# EEPROM.net
KiCad netlist of a schematic drawn in Altium Designer
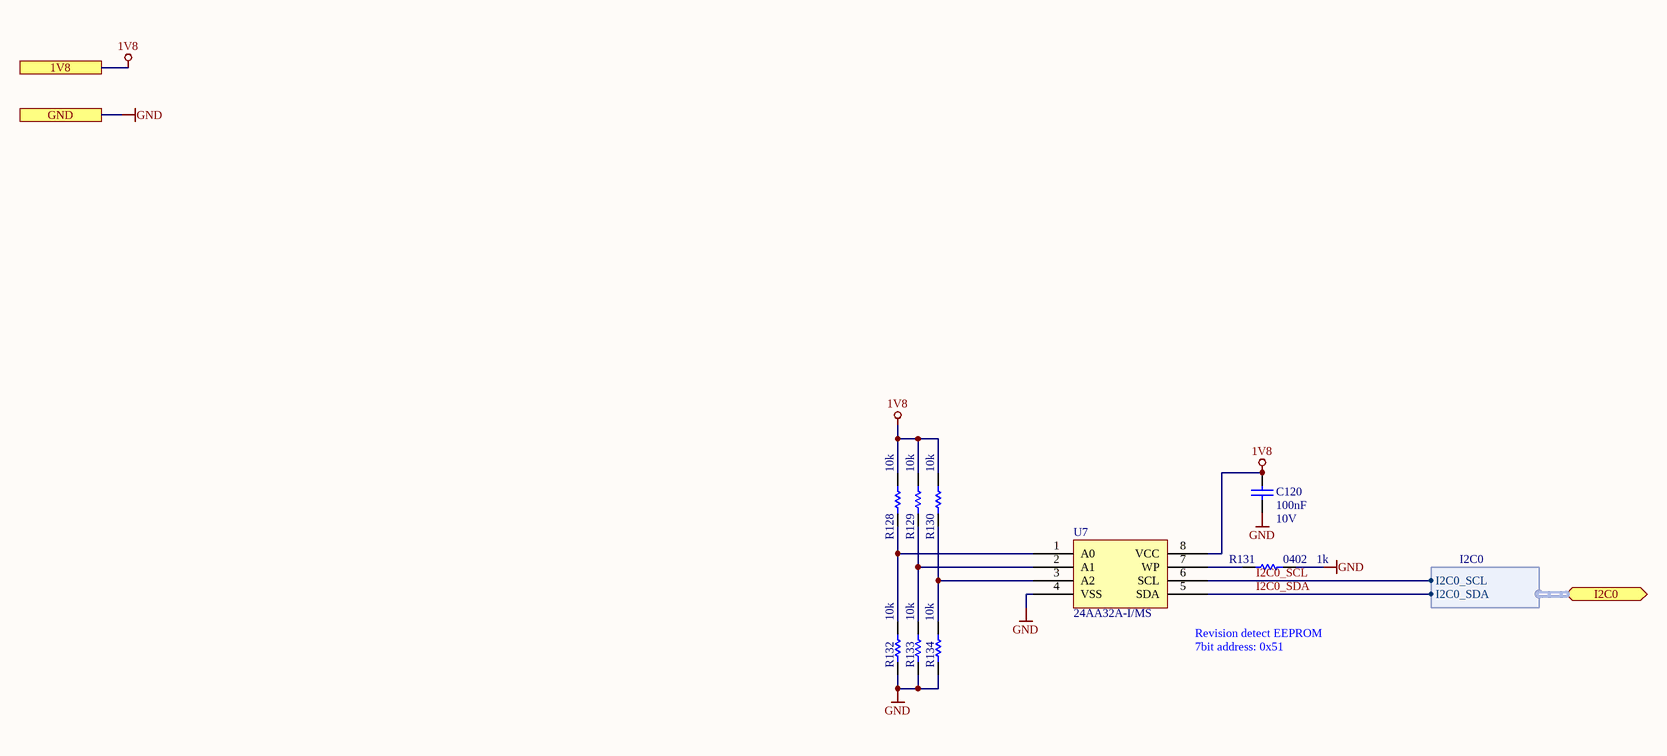
[diagram p0: EEPROM.SchDoc]

(export (version "E")
  (design (tool "Eeschema 10.0.6"))
  (components
    (comp (ref "C120")
      (value "100nF")
      (footprint "CAPC0402(1005)70_L")
      (description "CAP CER 0.1UF 10V X7R 0402 5%")
      (fields
        (field (name "TOLERANCE") "5%")
        (field (name "VOLTAGE RATING") "10V")
        (field (name "Comment") "GRM155R71A104JA01D")
      )
      (libsource (lib "Luxonis LLC") (part "GRM188R61C475KAAJD"))
    )
    (comp (ref "R128")
      (value "10k")
      (footprint "RESC0402(1005)_L")
      (description "RES SMD 10K OHM 1% 1/16W 0402")
      (fields (field (name "TOLERANCE") "1%") (field (name "Comment") "RC0402FR-1310KL"))
      (libsource (lib "Luxonis LLC") (part "RC0402FR-0722RL_1"))
    )
    (comp (ref "R129")
      (value "10k")
      (footprint "RESC0402(1005)_L")
      (description "RES SMD 10K OHM 1% 1/16W 0402")
      (fields (field (name "TOLERANCE") "1%") (field (name "Comment") "RC0402FR-1310KL"))
      (libsource (lib "Luxonis LLC") (part "RC0402FR-0722RL_1"))
    )
    (comp (ref "R130")
      (value "10k")
      (footprint "RESC0402(1005)_L")
      (description "RES SMD 10K OHM 1% 1/16W 0402")
      (fields (field (name "TOLERANCE") "1%") (field (name "Comment") "RC0402FR-1310KL"))
      (libsource (lib "Luxonis LLC") (part "RC0402FR-0722RL_1"))
    )
    (comp (ref "R131")
      (value "1k")
      (footprint "RESC0402(1005)_L")
      (description "RES SMD 1K OHM 1% 1/16W 0402")
      (fields
        (field (name "CASE/PACKAGE") "0402")
        (field (name "TOLERANCE") "1%")
        (field (name "Comment") "RC0402FR-071KL")
      )
      (libsource (lib "Luxonis LLC") (part "Default resistor symbol"))
    )
    (comp (ref "R132")
      (value "10k")
      (footprint "RESC0402(1005)_L")
      (description "RES SMD 10K OHM 1% 1/16W 0402")
      (fields (field (name "TOLERANCE") "1%") (field (name "Comment") "RC0402FR-1310KL"))
      (libsource (lib "Luxonis LLC") (part "RC0402FR-0722RL_1"))
    )
    (comp (ref "R133")
      (value "10k")
      (footprint "RESC0402(1005)_L")
      (description "RES SMD 10K OHM 1% 1/16W 0402")
      (fields (field (name "TOLERANCE") "1%") (field (name "Comment") "RC0402FR-1310KL"))
      (libsource (lib "Luxonis LLC") (part "RC0402FR-0722RL_1"))
    )
    (comp (ref "R134")
      (value "10k")
      (footprint "RESC0402(1005)_L")
      (description "RES SMD 10K OHM 1% 1/16W 0402")
      (fields (field (name "TOLERANCE") "1%") (field (name "Comment") "RC0402FR-1310KL"))
      (libsource (lib "Luxonis LLC") (part "RC0402FR-0722RL_1"))
    )
    (comp (ref "U7")
      (value "24AA32A-I/MS")
      (footprint "24AA32A-I/MS")
      (description "IC EEPROM 32K I2C 400KHZ 8MSOP Memory IC 32Kb (4K x 8) I²C 400kHz 900ns 8-MSOP")
      (libsource (lib "Luxonis LLC") (part "24AA32A-I/MS"))
    )
  )
  (nets
    (net (code "2") (name "/I2C0_SCL") (class "Default")
      (node (ref "U7") (pin "6") (pinfunction "SCL_6") (pintype "passive"))
    )
    (net (code "3") (name "/I2C0_SDA") (class "Default")
      (node (ref "U7") (pin "5") (pinfunction "SDA_5") (pintype "passive"))
    )
    (net (code "5") (name "1V8") (class "Default")
      (node (ref "C120") (pin "2") (pinfunction "2_2") (pintype "passive"))
      (node (ref "R128") (pin "2") (pinfunction "2_2") (pintype "passive"))
      (node (ref "R129") (pin "2") (pinfunction "2_2") (pintype "passive"))
      (node (ref "R130") (pin "2") (pinfunction "2_2") (pintype "passive"))
      (node (ref "U7") (pin "8") (pinfunction "VCC_8") (pintype "passive"))
    )
    (net (code "6") (name "GND") (class "Default")
      (node (ref "C120") (pin "1") (pinfunction "1_1") (pintype "passive"))
      (node (ref "R131") (pin "1") (pinfunction "1_1") (pintype "passive"))
      (node (ref "R132") (pin "1") (pinfunction "1_1") (pintype "passive"))
      (node (ref "R133") (pin "1") (pinfunction "1_1") (pintype "passive"))
      (node (ref "R134") (pin "1") (pinfunction "1_1") (pintype "passive"))
      (node (ref "U7") (pin "4") (pinfunction "VSS_4") (pintype "passive"))
    )
    (net (code "7") (name "Net-(U7-A0)") (class "Default")
      (node (ref "R128") (pin "1") (pinfunction "1_1") (pintype "passive"))
      (node (ref "R132") (pin "2") (pinfunction "2_2") (pintype "passive"))
      (node (ref "U7") (pin "1") (pinfunction "A0_1") (pintype "passive"))
    )
    (net (code "8") (name "Net-(U7-A1)") (class "Default")
      (node (ref "R129") (pin "1") (pinfunction "1_1") (pintype "passive"))
      (node (ref "R133") (pin "2") (pinfunction "2_2") (pintype "passive"))
      (node (ref "U7") (pin "2") (pinfunction "A1_2") (pintype "passive"))
    )
    (net (code "9") (name "Net-(U7-A2)") (class "Default")
      (node (ref "R130") (pin "1") (pinfunction "1_1") (pintype "passive"))
      (node (ref "R134") (pin "2") (pinfunction "2_2") (pintype "passive"))
      (node (ref "U7") (pin "3") (pinfunction "A2_3") (pintype "passive"))
    )
    (net (code "10") (name "Net-(U7-WP)") (class "Default")
      (node (ref "R131") (pin "2") (pinfunction "2_2") (pintype "passive"))
      (node (ref "U7") (pin "7") (pinfunction "WP_7") (pintype "passive"))
    )
  )
)
